# main.net
KiCad netlist of a schematic drawn in Altium Designer
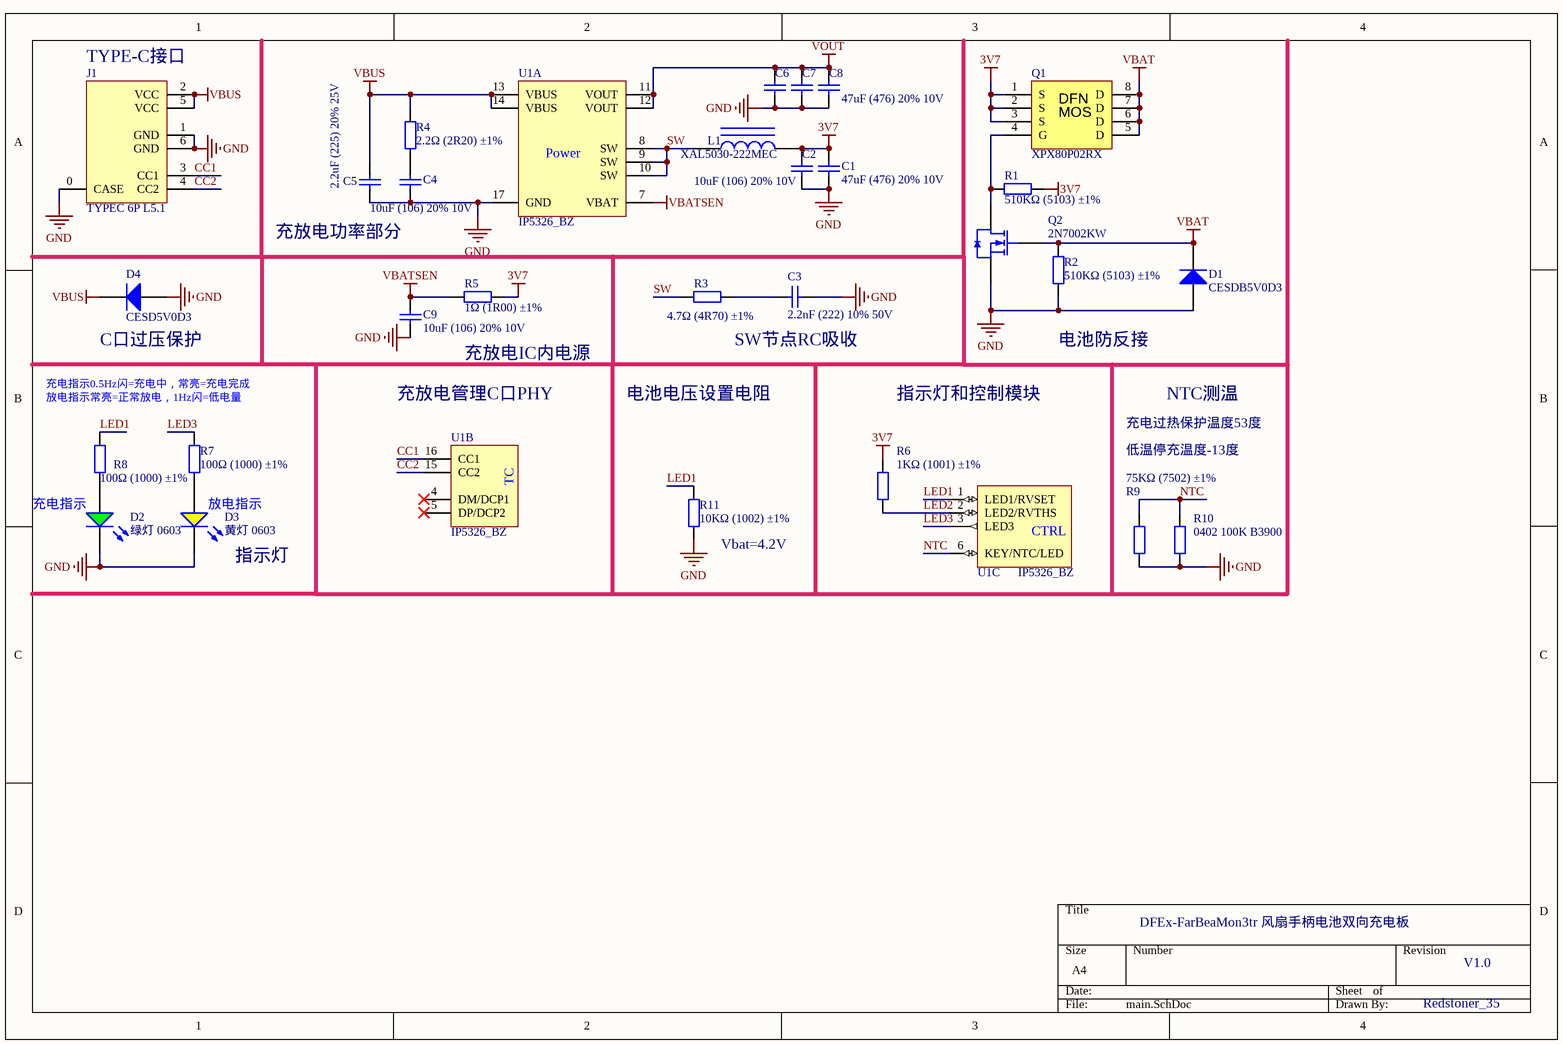
[diagram p0: main.SchDoc]

(export (version "E")
  (design (tool "Eeschema 10.0.6"))
  (components
    (comp (ref "C1")
      (value "47uF (476) 20% 10V")
      (footprint "0805_C")
      (description "贴片电容")
      (libsource (lib "Miscellaneous Devices LC") (part "0805 22uF (226) 20% 25V"))
    )
    (comp (ref "C2")
      (value "10uF (106) 20% 10V")
      (footprint "0402_C")
      (description "贴片电容")
      (libsource (lib "Miscellaneous Devices LC") (part "0402 10uF (106) 20% 6.3V"))
    )
    (comp (ref "C3")
      (value "2.2nF (222) 10% 50V")
      (footprint "0402_C")
      (description "贴片电容")
      (libsource (lib "Miscellaneous Devices LC") (part "0402 2.2nF (222) 10% 50V"))
    )
    (comp (ref "C4")
      (value "10uF (106) 20% 10V")
      (footprint "0402_C")
      (description "贴片电容")
      (libsource (lib "Miscellaneous Devices LC") (part "0402 10uF (106) 20% 6.3V"))
    )
    (comp (ref "C5")
      (value "2.2uF (225) 20% 25V")
      (footprint "0402_C")
      (description "贴片电容")
      (libsource (lib "Miscellaneous Devices LC") (part "0402 1.0uF (105) 10% 25V"))
    )
    (comp (ref "C6")
      (value "47uF (476) 20% 10V")
      (footprint "0805_C")
      (description "贴片电容")
      (libsource (lib "Miscellaneous Devices LC") (part "0805 22uF (226) 20% 25V"))
    )
    (comp (ref "C7")
      (value "47uF (476) 20% 10V")
      (footprint "0805_C")
      (description "贴片电容")
      (libsource (lib "Miscellaneous Devices LC") (part "0805 22uF (226) 20% 25V"))
    )
    (comp (ref "C8")
      (value "47uF (476) 20% 10V")
      (footprint "0805_C")
      (description "贴片电容")
      (libsource (lib "Miscellaneous Devices LC") (part "0805 22uF (226) 20% 25V"))
    )
    (comp (ref "C9")
      (value "10uF (106) 20% 10V")
      (footprint "0402_C")
      (description "贴片电容")
      (libsource (lib "Miscellaneous Devices LC") (part "0402 10uF (106) 20% 6.3V"))
    )
    (comp (ref "D1")
      (value "CESDB5V0D3")
      (footprint "SOD-323")
      (description "5V额定工作电压，6.2V击穿电压双向TVS管，SOD-323")
      (libsource (lib "Miscellaneous Devices LC") (part "SOD-323 1N4148WS T4"))
    )
    (comp (ref "D2")
      (value "绿灯 0603")
      (footprint "0603_LED_S1")
      (description "发光二极管")
      (libsource (lib "Miscellaneous Devices LC") (part "0603 绿灯"))
    )
    (comp (ref "D3")
      (value "黄灯 0603")
      (footprint "0603_LED_S1")
      (description "发光二极管")
      (libsource (lib "Miscellaneous Devices LC") (part "0603 黄灯"))
    )
    (comp (ref "D4")
      (value "CESD5V0D3")
      (footprint "SOD-323")
      (description "5V额定工作电压，6.2V击穿电压双向TVS管，SOD-323")
      (libsource (lib "Miscellaneous Devices LC") (part "SOD-323 1N4148WS T4"))
    )
    (comp (ref "J1")
      (value "TYPEC 6P L5.1")
      (footprint "TYPEC 6P两脚插板SMT L5.1")
      (description "TYPEC连接器 6P 2脚插板SMT 5.1长度")
      (libsource (lib "custom") (part "TYPEC 6P"))
    )
    (comp (ref "L1")
      (value "XAL5030-222MEC")
      (footprint "FEXL0520A-***M")
      (description "线艺XAL5030 2.2uH一体成型T-Core电感")
      (fields (field (name "PUBLISHER") "Altium Limited"))
      (libsource (lib "Miscellaneous Devices") (part "Inductor Iron"))
    )
    (comp (ref "Q1")
      (value "XPX80P02RX")
      (footprint "DFN-8_L3.0-W3.0-P0.65-BL")
      (description "PDFN3x3 20V 80A 4..0mΩ [P-Ch MOSFET")
      (libsource (lib "custom") (part "SON/DFN5x6 MOS"))
    )
    (comp (ref "Q2")
      (value "2N7002KW")
      (footprint "SC70-3")
      (description "单N沟道MOSFET(场效应管)")
      (libsource (lib "Miscellaneous Devices LC") (part "2N7002 7002"))
    )
    (comp (ref "R1")
      (value "510KΩ (5103) ±1%")
      (footprint "0402_R")
      (description "贴片电阻")
      (libsource (lib "") (part "0402 510KΩ (5103) 1%_1"))
    )
    (comp (ref "R2")
      (value "510KΩ (5103) ±1%")
      (footprint "0402_R")
      (description "贴片电阻")
      (libsource (lib "Miscellaneous Devices LC") (part "0402 510KΩ (5103) 1%"))
    )
    (comp (ref "R3")
      (value "4.7Ω (4R70) ±1%")
      (footprint "0402_R")
      (description "贴片电阻")
      (libsource (lib "Miscellaneous Devices LC") (part "0402 4.7KΩ (4701) 1%"))
    )
    (comp (ref "R4")
      (value "2.2Ω (2R20) ±1%")
      (footprint "0402_R")
      (description "贴片电阻")
      (libsource (lib "") (part "0402 4.7KΩ (4701) 1%_1"))
    )
    (comp (ref "R5")
      (value "1Ω (1R00) ±1%")
      (footprint "0805_R")
      (description "贴片电阻")
      (libsource (lib "Miscellaneous Devices LC") (part "0805 1Ω (1R00) 1%"))
    )
    (comp (ref "R6")
      (value "1KΩ (1001) ±1%")
      (footprint "0402_R")
      (description "贴片电阻")
      (libsource (lib "Miscellaneous Devices LC") (part "0402 1KΩ (1001) 1%"))
    )
    (comp (ref "R7")
      (value "100Ω (1000) ±1%")
      (footprint "0402_R")
      (description "贴片电阻")
      (libsource (lib "Miscellaneous Devices LC") (part "0402 100Ω (1000) 1%"))
    )
    (comp (ref "R8")
      (value "100Ω (1000) ±1%")
      (footprint "0402_R")
      (description "贴片电阻")
      (libsource (lib "Miscellaneous Devices LC") (part "0402 100Ω (1000) 1%"))
    )
    (comp (ref "R9")
      (value "75KΩ (7502) ±1%")
      (footprint "0402_R")
      (description "贴片电阻")
      (libsource (lib "Miscellaneous Devices LC") (part "0402 150KΩ (1503) 1%"))
    )
    (comp (ref "R10")
      (value "0402 100K B3900")
      (footprint "0402_R")
      (description "0402贴片NTC热敏电阻 B4150 100K 1%")
      (libsource (lib "Miscellaneous Devices LC") (part "0402 100KΩ (1003) 1%"))
    )
    (comp (ref "R11")
      (value "10KΩ (1002) ±1%")
      (footprint "0402_R")
      (description "贴片电阻")
      (libsource (lib "Miscellaneous Devices LC") (part "0402 10KΩ (1002) 1%"))
    )
    (comp (ref "U1")
      (value "IP5326_BZ")
      (footprint "QFN33-16L-IP5326")
      (description "集成TYPC-C协议的2.4A 5V充放电移动电源SoC QFN3*3封装")
      (libsource (lib "custom") (part "IP5326_BZ"))
    )
  )
  (nets
    (net (code "1") (name "/CC1") (class "Default")
      (node (ref "J1") (pin "3") (pinfunction "CC1_3") (pintype "passive"))
      (node (ref "U1") (pin "16") (pinfunction "CC1_16") (pintype "passive"))
    )
    (net (code "2") (name "/CC2") (class "Default")
      (node (ref "J1") (pin "4") (pinfunction "CC2_4") (pintype "passive"))
      (node (ref "U1") (pin "15") (pinfunction "CC2_15") (pintype "passive"))
    )
    (net (code "3") (name "/LED1") (class "Default")
      (node (ref "R11") (pin "2") (pinfunction "2_2") (pintype "passive"))
      (node (ref "R8") (pin "2") (pinfunction "2_2") (pintype "passive"))
      (node (ref "U1") (pin "1") (pinfunction "LED1/RVSET_1") (pintype "bidirectional"))
    )
    (net (code "4") (name "/LED2") (class "Default")
      (node (ref "R6") (pin "2") (pinfunction "2_2") (pintype "passive"))
      (node (ref "U1") (pin "2") (pinfunction "LED2/RVTHS_2") (pintype "bidirectional"))
    )
    (net (code "5") (name "/LED3") (class "Default")
      (node (ref "R7") (pin "2") (pinfunction "2_2") (pintype "passive"))
      (node (ref "U1") (pin "3") (pinfunction "LED3_3") (pintype "output"))
    )
    (net (code "6") (name "/NTC") (class "Default")
      (node (ref "R10") (pin "2") (pinfunction "2_2") (pintype "passive"))
      (node (ref "R9") (pin "2") (pinfunction "2_2") (pintype "passive"))
      (node (ref "U1") (pin "6") (pinfunction "KEY/NTC/LED_6") (pintype "bidirectional"))
    )
    (net (code "7") (name "/SW") (class "Default")
      (node (ref "L1") (pin "1") (pinfunction "1_1") (pintype "passive"))
      (node (ref "R3") (pin "2") (pinfunction "2_2") (pintype "passive"))
      (node (ref "U1") (pin "10") (pinfunction "SW_10") (pintype "power_in"))
      (node (ref "U1") (pin "8") (pinfunction "SW_8") (pintype "power_in"))
      (node (ref "U1") (pin "9") (pinfunction "SW_9") (pintype "power_in"))
    )
    (net (code "8") (name "3V7") (class "Default")
      (node (ref "C1") (pin "2") (pinfunction "2_2") (pintype "passive"))
      (node (ref "C2") (pin "2") (pinfunction "2_2") (pintype "passive"))
      (node (ref "L1") (pin "2") (pinfunction "2_2") (pintype "passive"))
      (node (ref "Q1") (pin "1") (pinfunction "S_1") (pintype "passive"))
      (node (ref "Q1") (pin "2") (pinfunction "S_2") (pintype "passive"))
      (node (ref "Q1") (pin "3") (pinfunction "S_3") (pintype "passive"))
      (node (ref "R1") (pin "1") (pinfunction "1_1") (pintype "passive"))
      (node (ref "R5") (pin "2") (pinfunction "2_2") (pintype "passive"))
      (node (ref "R6") (pin "1") (pinfunction "1_1") (pintype "passive"))
    )
    (net (code "9") (name "GND") (class "Default")
      (node (ref "C1") (pin "1") (pinfunction "1_1") (pintype "passive"))
      (node (ref "C2") (pin "1") (pinfunction "1_1") (pintype "passive"))
      (node (ref "C3") (pin "1") (pinfunction "1_1") (pintype "passive"))
      (node (ref "C4") (pin "1") (pinfunction "1_1") (pintype "passive"))
      (node (ref "C5") (pin "1") (pinfunction "1_1") (pintype "passive"))
      (node (ref "C6") (pin "1") (pinfunction "1_1") (pintype "passive"))
      (node (ref "C7") (pin "1") (pinfunction "1_1") (pintype "passive"))
      (node (ref "C8") (pin "1") (pinfunction "1_1") (pintype "passive"))
      (node (ref "C9") (pin "1") (pinfunction "1_1") (pintype "passive"))
      (node (ref "D1") (pin "1") (pinfunction "A_1") (pintype "passive"))
      (node (ref "D2") (pin "K") (pinfunction "K_K") (pintype "passive"))
      (node (ref "D3") (pin "K") (pinfunction "K_K") (pintype "passive"))
      (node (ref "D4") (pin "1") (pinfunction "A_1") (pintype "passive"))
      (node (ref "J1") (pin "0") (pinfunction "CASE_0") (pintype "passive"))
      (node (ref "J1") (pin "1") (pinfunction "GND_1") (pintype "power_in"))
      (node (ref "J1") (pin "6") (pinfunction "GND_6") (pintype "power_in"))
      (node (ref "Q2") (pin "2") (pinfunction "S_2") (pintype "passive"))
      (node (ref "R10") (pin "1") (pinfunction "1_1") (pintype "passive"))
      (node (ref "R11") (pin "1") (pinfunction "1_1") (pintype "passive"))
      (node (ref "R2") (pin "1") (pinfunction "1_1") (pintype "passive"))
      (node (ref "R9") (pin "1") (pinfunction "1_1") (pintype "passive"))
      (node (ref "U1") (pin "17") (pinfunction "GND_17") (pintype "power_in"))
    )
    (net (code "10") (name "Net-(C3-Pad2)") (class "Default")
      (node (ref "C3") (pin "2") (pinfunction "2_2") (pintype "passive"))
      (node (ref "R3") (pin "1") (pinfunction "1_1") (pintype "passive"))
    )
    (net (code "11") (name "Net-(C4-Pad2)") (class "Default")
      (node (ref "C4") (pin "2") (pinfunction "2_2") (pintype "passive"))
      (node (ref "R4") (pin "1") (pinfunction "1_1") (pintype "passive"))
    )
    (net (code "12") (name "Net-(D2-PadA)") (class "Default")
      (node (ref "D2") (pin "A") (pinfunction "A_A") (pintype "passive"))
      (node (ref "R8") (pin "1") (pinfunction "1_1") (pintype "passive"))
    )
    (net (code "13") (name "Net-(D3-PadA)") (class "Default")
      (node (ref "D3") (pin "A") (pinfunction "A_A") (pintype "passive"))
      (node (ref "R7") (pin "1") (pinfunction "1_1") (pintype "passive"))
    )
    (net (code "14") (name "Net-(Q1-G)") (class "Default")
      (node (ref "Q1") (pin "4") (pinfunction "G_4") (pintype "passive"))
      (node (ref "Q2") (pin "3") (pinfunction "D_3") (pintype "passive"))
      (node (ref "R1") (pin "2") (pinfunction "2_2") (pintype "passive"))
    )
    (net (code "15") (name "VBAT") (class "Default")
      (node (ref "D1") (pin "2") (pinfunction "K_2") (pintype "passive"))
      (node (ref "Q1") (pin "5") (pinfunction "D_5") (pintype "passive"))
      (node (ref "Q1") (pin "6") (pinfunction "D_6") (pintype "passive"))
      (node (ref "Q1") (pin "7") (pinfunction "D_7") (pintype "passive"))
      (node (ref "Q1") (pin "8") (pinfunction "D_8") (pintype "passive"))
      (node (ref "Q2") (pin "1") (pinfunction "G_1") (pintype "passive"))
      (node (ref "R2") (pin "2") (pinfunction "2_2") (pintype "passive"))
    )
    (net (code "16") (name "VBATSEN") (class "Default")
      (node (ref "C9") (pin "2") (pinfunction "2_2") (pintype "passive"))
      (node (ref "R5") (pin "1") (pinfunction "1_1") (pintype "passive"))
      (node (ref "U1") (pin "7") (pinfunction "VBAT_7") (pintype "power_in"))
    )
    (net (code "17") (name "VBUS") (class "Default")
      (node (ref "C5") (pin "2") (pinfunction "2_2") (pintype "passive"))
      (node (ref "D4") (pin "2") (pinfunction "K_2") (pintype "passive"))
      (node (ref "J1") (pin "2") (pinfunction "VCC_2") (pintype "power_in"))
      (node (ref "J1") (pin "5") (pinfunction "VCC_5") (pintype "power_in"))
      (node (ref "R4") (pin "2") (pinfunction "2_2") (pintype "passive"))
      (node (ref "U1") (pin "13") (pinfunction "VBUS_13") (pintype "power_in"))
      (node (ref "U1") (pin "14") (pinfunction "VBUS_14") (pintype "power_in"))
    )
    (net (code "18") (name "VOUT") (class "Default")
      (node (ref "C6") (pin "2") (pinfunction "2_2") (pintype "passive"))
      (node (ref "C7") (pin "2") (pinfunction "2_2") (pintype "passive"))
      (node (ref "C8") (pin "2") (pinfunction "2_2") (pintype "passive"))
      (node (ref "U1") (pin "11") (pinfunction "VOUT_11") (pintype "power_in"))
      (node (ref "U1") (pin "12") (pinfunction "VOUT_12") (pintype "power_in"))
    )
    (net (code "19") (name "unconnected-(U1B-DM{slash}DCP1-Pad4)") (class "Default")
      (node (ref "U1") (pin "4") (pinfunction "DM/DCP1_4") (pintype "passive+no_connect"))
    )
    (net (code "20") (name "unconnected-(U1B-DP{slash}DCP2-Pad5)") (class "Default")
      (node (ref "U1") (pin "5") (pinfunction "DP/DCP2_5") (pintype "passive+no_connect"))
    )
  )
)
